# BMS_Current_Sense.net
KiCad netlist of a schematic drawn in Altium Designer
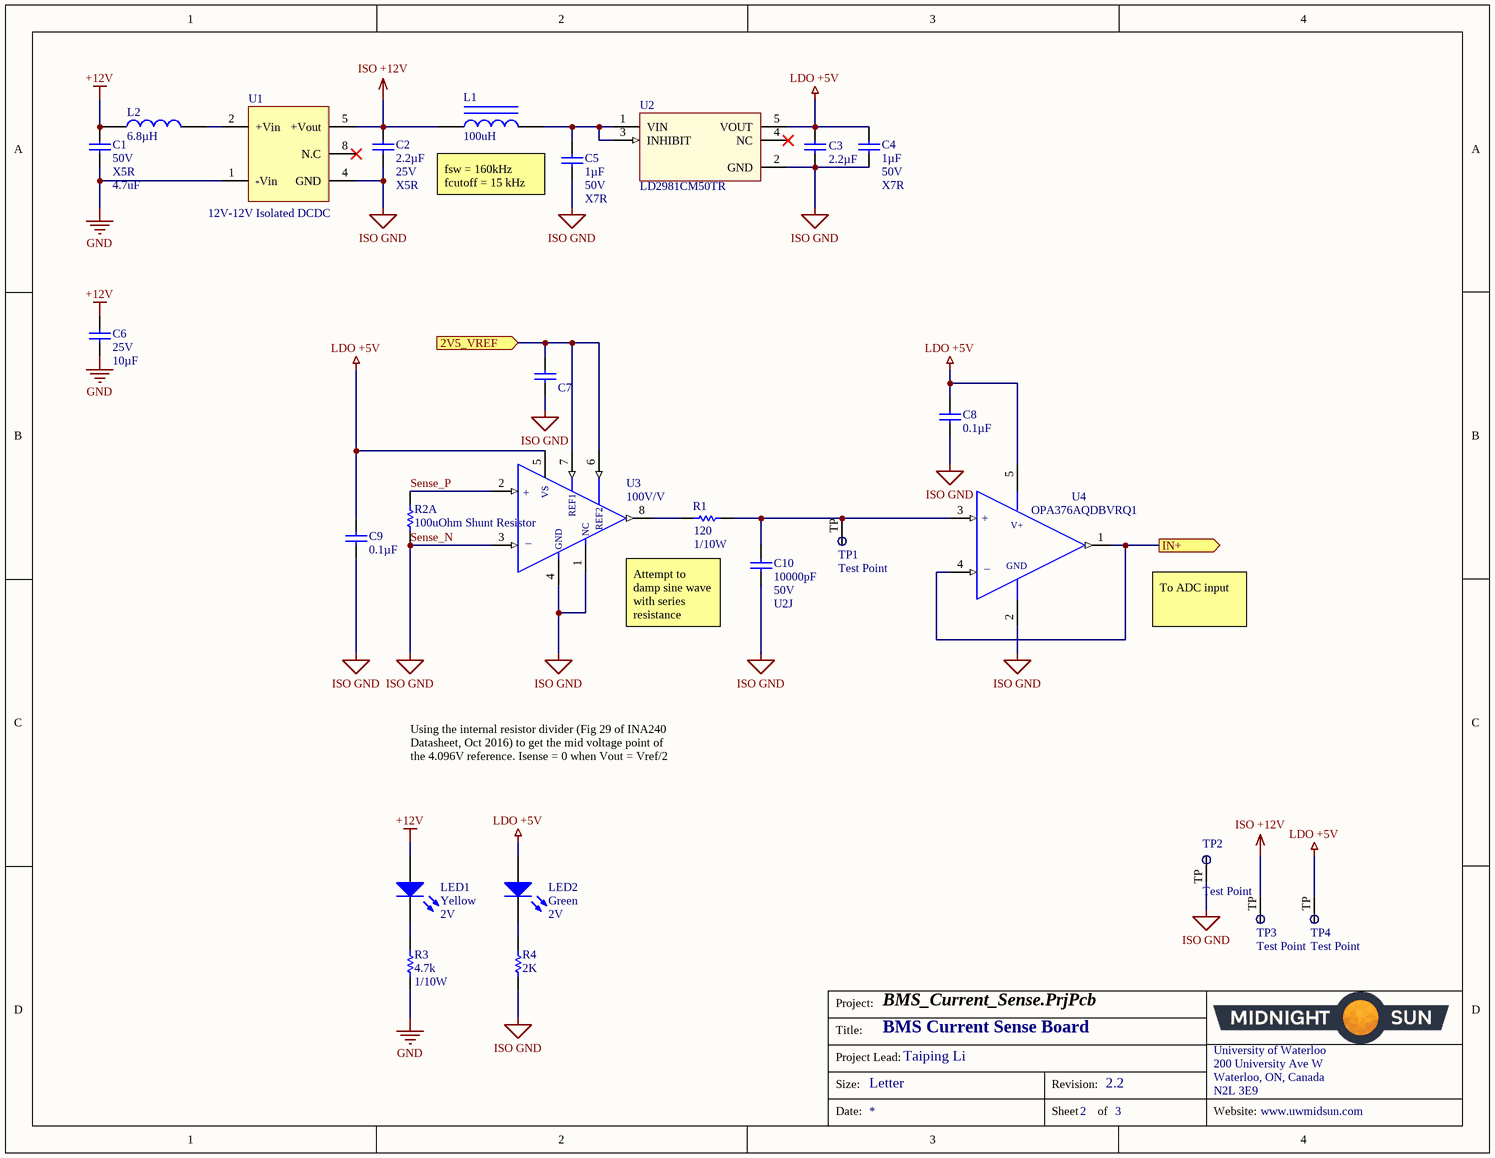
[diagram p0: BMS_Current_Sense.SchDoc]

(export (version "E")
  (design (tool "Eeschema 10.0.6"))
  (components
    (comp (ref "C1")
      (value "4.7uF")
      (footprint "CAP, 0805")
      (description "4.7µF ±20% 50V Ceramic Capacitor X5R 0805 (2012 Metric)")
      (fields
        (field (name "TOLERANCE") "±20%")
        (field (name "VOLTAGE - RATED") "50V")
        (field (name "TEMPERATURE COEFFICIENT") "X5R")
        (field (name "Comment") "CAP CER 4.7UF 50V 10% X5R 0805")
      )
      (libsource (lib "Schematic Diagrams") (part "CAP CER 4.7UF 50V 10% X5R 0805"))
    )
    (comp (ref "C2")
      (value "CAP CER 2.2UF 25V 10% X5R 0603")
      (footprint "CAP, 0603")
      (description "2.2µF ±10% 25V Ceramic Capacitor X5R 0603 (1608 Metric)")
      (fields
        (field (name "TOLERANCE") "±10%")
        (field (name "CAPACITANCE") "2.2µF")
        (field (name "VOLTAGE") "25V")
        (field (name "TEMPERATURE COEFFICIENT") "X5R")
      )
      (libsource (lib "Schematic Diagrams") (part "CAP CER 2.2UF 25V 10% X5R 0603"))
    )
    (comp (ref "C3")
      (value "CAP CER 2.2UF 25V 10% X5R 0603")
      (footprint "CAP, 0603")
      (description "2.2µF ±10% 25V Ceramic Capacitor X5R 0603 (1608 Metric)")
      (fields
        (field (name "TOLERANCE") "±10%")
        (field (name "CAPACITANCE") "2.2µF")
        (field (name "VOLTAGE") "25V")
      )
      (libsource (lib "Schematic Diagrams") (part "CAP CER 2.2UF 25V 10% X5R 0603"))
    )
    (comp (ref "C4")
      (value "CAP CER 1UF 50V 10% X7R 0603")
      (footprint "CAP, 0603")
      (description "1µF ±10% 50V Ceramic Capacitor X7R 0603 (1608 Metric)")
      (fields
        (field (name "TOLERANCE") "±10%")
        (field (name "CAPACITANCE") "1µF")
        (field (name "VOLTAGE") "50V")
        (field (name "TEMPERATURE COEFFICIENT") "X7R")
      )
      (libsource (lib "Schematic Diagrams") (part "CAP CER 1UF 50V 10% X7R 0603"))
    )
    (comp (ref "C5")
      (value "CAP CER 1UF 50V 10% X7R 0603")
      (footprint "CAP, 0603")
      (description "1µF ±10% 50V Ceramic Capacitor X7R 0603 (1608 Metric)")
      (fields
        (field (name "TOLERANCE") "±10%")
        (field (name "CAPACITANCE") "1µF")
        (field (name "VOLTAGE") "50V")
        (field (name "TEMPERATURE COEFFICIENT") "X7R")
      )
      (libsource (lib "Schematic Diagrams") (part "CAP CER 1UF 50V 10% X7R 0603"))
    )
    (comp (ref "C6")
      (value "CAP CER 10uF 25V 10% X5R 0805")
      (footprint "CAP, 0805")
      (description "10µF ±10% 25V Ceramic Capacitor X5R 0805 (2012 Metric)")
      (fields
        (field (name "MANUFACTURER") "Murata Electronics North America")
        (field (name "MANUFACTURER PART NUMBER") "GRM21BR61E106KA73L")
        (field (name "VOLTAGE - RATED") "25V")
        (field (name "CAPACITANCE") "10µF")
      )
      (libsource (lib "Schematic Diagrams") (part "CAP CER 10uF 25V 10% X5R 0805"))
    )
    (comp (ref "C7")
      (value "CAP CER 0.022UF 50V 10% X7R 0603")
      (footprint "CAP, 0603")
      (description "0.022µF ±10% 50V Ceramic Capacitor X7R 0603 (1608 Metric)")
      (fields (field (name "TOLERANCE") "±10%"))
      (libsource (lib "Schematic Diagrams") (part "CAP CER 0.022UF 50V 10% X7R 0603"))
    )
    (comp (ref "C8")
      (value "CAP CER 0.1UF 50V 10% X7R 0603")
      (footprint "CAP, 0603")
      (description "0.10µF ±10% 50V Ceramic Capacitor X7R 0603 (1608 Metric)")
      (fields
        (field (name "TOLERANCE") "±10%")
        (field (name "CAPACITANCE") "0.1µF")
        (field (name "VOLTAGE") "50V")
      )
      (libsource (lib "Schematic Diagrams") (part "CAP CER 0.1UF 50V 10% X7R 0603"))
    )
    (comp (ref "C9")
      (value "CAP CER 0.1UF 50V 10% X7R 0603")
      (footprint "CAP, 0603")
      (description "0.10µF ±10% 50V Ceramic Capacitor X7R 0603 (1608 Metric)")
      (fields
        (field (name "TOLERANCE") "±10%")
        (field (name "CAPACITANCE") "0.1µF")
        (field (name "VOLTAGE") "50V")
      )
      (libsource (lib "Schematic Diagrams") (part "CAP CER 0.1UF 50V 10% X7R 0603"))
    )
    (comp (ref "C10")
      (value "CAP CER 10nF 50V 5% X7R 0603")
      (footprint "CAP, 0603")
      (description "10000pF ±5% 50V Ceramic Capacitor U2J 0603 (1608 Metric)")
      (fields
        (field (name "TOLERANCE") "±5%")
        (field (name "CAPACITANCE") "10000pF")
        (field (name "VOLTAGE") "50V")
        (field (name "TEMPERATURE COEFFICIENT") "U2J")
      )
      (libsource (lib "Schematic Diagrams") (part "CAP CER 10nF 50V 5% X7R 0603"))
    )
    (comp (ref "L1")
      (value "100uH")
      (footprint "1210")
      (description "100µH Unshielded Wirewound Inductor 60mA 11 Ohm Max 1210 (3225 Metric)")
      (fields
        (field (name "MANUFACTURER") "EPCOS (TDK)")
        (field (name "MANUFACTURER PART NUMBER") "B82422T1104J000")
      )
      (libsource (lib "Schematic Diagrams") (part "IND 100uH 60mA 5% 1210"))
    )
    (comp (ref "L2")
      (value "IND 6.8uH 260mA 20% 1210")
      (footprint "NLFV32T-6R8M-EF/IND 6.8uH")
      (description "6.8µH Shielded Wirewound Inductor 260mA 204 mOhm Max 1210 (3225 Metric)")
      (fields (field (name "TOLERANCE") "±20%") (field (name "INDUCTANCE") "6.8µH"))
      (libsource (lib "Schematic Diagrams") (part "IND 6.8uH 260mA 20% 1210"))
    )
    (comp (ref "LED1")
      (value "LED YELLOW CLEAR 2.1V 0603")
      (footprint "LED_0603")
      (description "Yellow 590nm LED Indication - Discrete 2V 0603 (1608 Metric)")
      (fields
        (field (name "MANUFACTURER") "Wurth Electronics Inc.")
        (field (name "MANUFACTURER PART NUMBER") "150060YS75000")
        (field (name "COLOR") "Yellow")
        (field (name "VOLTAGE - FORWARD (VF) (TYP)") "2V")
      )
      (libsource (lib "Schematic Diagrams") (part "LED YELLOW CLEAR 2.1V 0603"))
    )
    (comp (ref "LED2")
      (value "LED GREEN CLEAR 2V 0603")
      (footprint "LED_0603")
      (description "Green 572nm LED Indication - Discrete 2V 0603 (1608 Metric)")
      (fields
        (field (name "MANUFACTURER") "Wurth Electronics Inc.")
        (field (name "MANUFACTURER PART NUMBER") "150060VS75000")
        (field (name "COLOR") "Green")
        (field (name "VOLTAGE - FORWARD (VF) (TYP)") "2V")
      )
      (libsource (lib "Schematic Diagrams") (part "LED GREEN CLEAR 2V 0603"))
    )
    (comp (ref "R1")
      (value "RES 120 OHM 1% 1/10W 0603")
      (footprint "RES, 0603")
      (description "RES SMD 120 OHM 1% 1/10W 0603")
      (fields
        (field (name "TOLERANCE") "±1%")
        (field (name "RESISTANCE") "120")
        (field (name "POWER") "1/10W")
      )
      (libsource (lib "Schematic Diagrams") (part "RES 120 OHM 1% 1/10W 0603"))
    )
    (comp (ref "R2")
      (value "100uOhm Shunt Resistor")
      (footprint "RES SHUNT 100UOHM 60MM")
      (fields (field (name "TOLERANCE") "±5%"))
      (libsource (lib "Schematic Diagrams") (part "RES SHUNT 100UOHM 5% 36W 60MM"))
    )
    (comp (ref "R3")
      (value "RES 4.7K OHM 1% 1/10W 0603")
      (footprint "RES, 0603")
      (description "4.7k Ohm ±1% 0.1W, 1/10W Chip Resistor 0603 (1608 Metric) Moisture Resistant Thick Film")
      (fields
        (field (name "TOLERANCE") "±1%")
        (field (name "RESISTANCE (OHMS)") "4.7k")
        (field (name "POWER (WATTS)") "1/10W")
      )
      (libsource (lib "Schematic Diagrams") (part "RES 4.7K OHM 1% 1/10W 0603"))
    )
    (comp (ref "R4")
      (value "2K")
      (footprint "RES, 0603")
      (description "2k Ohm ±1% 0.1W, 1/10W Chip Resistor 0603 (1608 Metric) Moisture Resistant Thick Film")
      (fields
        (field (name "MANUFACTURER") "Yageo")
        (field (name "MANUFACTURER PART NUMBER") "RC0603FR-072KL")
      )
      (libsource (lib "Schematic Diagrams") (part "RES 2K OHM 1% 1/10W 0603"))
    )
    (comp (ref "TP1")
      (value "Test Point")
      (footprint "Test Point")
      (libsource (lib "Schematic Diagrams") (part "Test Point"))
    )
    (comp (ref "TP2")
      (value "Test Point")
      (footprint "Test Point")
      (libsource (lib "Schematic Diagrams") (part "Test Point"))
    )
    (comp (ref "TP3")
      (value "Test Point")
      (footprint "Test Point")
      (libsource (lib "Schematic Diagrams") (part "Test Point"))
    )
    (comp (ref "TP4")
      (value "Test Point")
      (footprint "Test Point")
      (libsource (lib "Schematic Diagrams") (part "Test Point"))
    )
    (comp (ref "U1")
      (value "IC DCDC ISOLATED 12V 1W 8-SMD 5-LEAD")
      (footprint "IC, Isolated DCDC")
      (description "Isolated Module DC DC Converter 1 Output 12V 84mA 10.8V - 13.2V Input")
      (fields (field (name "POWER") "1W") (field (name "TYPE") "12V-12V Isolated DCDC"))
      (libsource (lib "Schematic Diagrams") (part "IC DCDC ISOLATED 12V 1W 8-SMD 5-LEAD"))
    )
    (comp (ref "U2")
      (value "IC REG LDO 5V 0.1A SOT23-5")
      (footprint "SOT95P280X145-5N")
      (description "Linear Voltage Regulator IC Positive Fixed Output 5V 100mA SOT-23-5")
      (fields (field (name "MANUFACTURER PART NUMBER 1") "LD2981CM50TR"))
      (libsource (lib "Schematic Diagrams") (part "IC REG LDO 5V 0.1A SOT23-5"))
    )
    (comp (ref "U3")
      (value "100V/V")
      (footprint "IC CURRENT AMPLIFIER INA240 TSSOP-8")
      (description "Current Sense Amplifier 1 Circuit 8-TSSOP")
      (libsource (lib "Schematic Diagrams") (part "IC CURRENT AMPLIFIER INA240 8-TSSOP"))
    )
    (comp (ref "U4")
      (value "IC OP AMP GEN PURPOSE RR 5.5MHZ SOT-23-5")
      (footprint "IC OP AMP GP RR 10MHZ SOT-23-5")
      (description "General Purpose Amplifier 1 Circuit Rail-to-Rail SOT-23-5")
      (fields
        (field (name "MANUFACTURER") "Texas Instruments")
        (field (name "MANUFACTURER PART NUMBER") "OPA376AQDBVRQ1")
      )
      (libsource (lib "Schematic Diagrams") (part "IC OP AMP GEN PURPOSE RR 5.5MHZ SOT-23-5"))
    )
  )
  (nets
    (net (code "1") (name "+12V") (class "Default")
      (node (ref "C1") (pin "1") (pinfunction "1_1") (pintype "passive"))
      (node (ref "C6") (pin "1") (pinfunction "1_1") (pintype "passive"))
      (node (ref "L2") (pin "1") (pinfunction "1_1") (pintype "passive"))
      (node (ref "LED1") (pin "1") (pinfunction "A_1") (pintype "passive"))
    )
    (net (code "2") (name "/2V5_VREF") (class "Default")
      (node (ref "C7") (pin "1") (pinfunction "1_1") (pintype "passive"))
      (node (ref "U3") (pin "6") (pinfunction "REF2_6") (pintype "input"))
      (node (ref "U3") (pin "7") (pinfunction "REF1_7") (pintype "input"))
    )
    (net (code "3") (name "/IN+") (class "Default")
      (node (ref "U4") (pin "1") (pinfunction "OUTPUT_1") (pintype "output"))
      (node (ref "U4") (pin "4") (pinfunction "-IN_4") (pintype "input"))
    )
    (net (code "4") (name "/Sense_P") (class "Default")
      (node (ref "R2") (pin "5") (pinfunction "5_5") (pintype "passive"))
      (node (ref "U3") (pin "2") (pinfunction "+IN_2") (pintype "input"))
    )
    (net (code "5") (name "GND") (class "Default")
      (node (ref "C1") (pin "2") (pinfunction "2_2") (pintype "passive"))
      (node (ref "C6") (pin "2") (pinfunction "2_2") (pintype "passive"))
      (node (ref "R3") (pin "2") (pinfunction "2_2") (pintype "passive"))
      (node (ref "U1") (pin "1") (pinfunction "-Vin_1") (pintype "passive"))
    )
    (net (code "6") (name "ISO +12V") (class "Default")
      (node (ref "C2") (pin "1") (pinfunction "1_1") (pintype "passive"))
      (node (ref "L1") (pin "1") (pinfunction "1_1") (pintype "passive"))
      (node (ref "TP3") (pin "TP") (pinfunction "1_TP") (pintype "passive"))
      (node (ref "U1") (pin "5") (pinfunction "+Vout_5") (pintype "passive"))
    )
    (net (code "7") (name "ISO GND") (class "Default")
      (node (ref "C10") (pin "2") (pinfunction "2_2") (pintype "passive"))
      (node (ref "C2") (pin "2") (pinfunction "2_2") (pintype "passive"))
      (node (ref "C3") (pin "2") (pinfunction "2_2") (pintype "passive"))
      (node (ref "C4") (pin "2") (pinfunction "2_2") (pintype "passive"))
      (node (ref "C5") (pin "2") (pinfunction "2_2") (pintype "passive"))
      (node (ref "C7") (pin "2") (pinfunction "2_2") (pintype "passive"))
      (node (ref "C8") (pin "2") (pinfunction "2_2") (pintype "passive"))
      (node (ref "C9") (pin "2") (pinfunction "2_2") (pintype "passive"))
      (node (ref "R2") (pin "6") (pinfunction "6_6") (pintype "passive"))
      (node (ref "R4") (pin "2") (pinfunction "2_2") (pintype "passive"))
      (node (ref "TP2") (pin "TP") (pinfunction "1_TP") (pintype "passive"))
      (node (ref "U1") (pin "4") (pinfunction "GND_4") (pintype "passive"))
      (node (ref "U2") (pin "2") (pinfunction "GND_2") (pintype "power_in"))
      (node (ref "U3") (pin "1") (pinfunction "NC_1") (pintype "power_in"))
      (node (ref "U3") (pin "3") (pinfunction "-IN_3") (pintype "input"))
      (node (ref "U3") (pin "4") (pinfunction "GND_4") (pintype "power_in"))
      (node (ref "U4") (pin "2") (pinfunction "VSS_2") (pintype "power_in"))
    )
    (net (code "8") (name "LDO +5V") (class "Default")
      (node (ref "C3") (pin "1") (pinfunction "1_1") (pintype "passive"))
      (node (ref "C4") (pin "1") (pinfunction "1_1") (pintype "passive"))
      (node (ref "C8") (pin "1") (pinfunction "1_1") (pintype "passive"))
      (node (ref "C9") (pin "1") (pinfunction "1_1") (pintype "passive"))
      (node (ref "LED2") (pin "1") (pinfunction "A_1") (pintype "passive"))
      (node (ref "TP4") (pin "TP") (pinfunction "1_TP") (pintype "passive"))
      (node (ref "U2") (pin "5") (pinfunction "VOUT_5") (pintype "power_in"))
      (node (ref "U3") (pin "5") (pinfunction "VS_5") (pintype "power_in"))
      (node (ref "U4") (pin "5") (pinfunction "VDD_5") (pintype "power_in"))
    )
    (net (code "9") (name "Net-(LED1-K)") (class "Default")
      (node (ref "LED1") (pin "2") (pinfunction "K_2") (pintype "passive"))
      (node (ref "R3") (pin "1") (pinfunction "1_1") (pintype "passive"))
    )
    (net (code "10") (name "Net-(LED2-K)") (class "Default")
      (node (ref "LED2") (pin "2") (pinfunction "K_2") (pintype "passive"))
      (node (ref "R4") (pin "1") (pinfunction "1_1") (pintype "passive"))
    )
    (net (code "11") (name "Net-(TP1-1)") (class "Default")
      (node (ref "C10") (pin "1") (pinfunction "1_1") (pintype "passive"))
      (node (ref "R1") (pin "2") (pinfunction "2_2") (pintype "passive"))
      (node (ref "TP1") (pin "TP") (pinfunction "1_TP") (pintype "passive"))
      (node (ref "U4") (pin "3") (pinfunction "+IN_3") (pintype "input"))
    )
    (net (code "12") (name "Net-(U1-+Vin)") (class "Default")
      (node (ref "L2") (pin "2") (pinfunction "2_2") (pintype "passive"))
      (node (ref "U1") (pin "2") (pinfunction "+Vin_2") (pintype "passive"))
    )
    (net (code "13") (name "Net-(U2-INHIBIT)") (class "Default")
      (node (ref "C5") (pin "1") (pinfunction "1_1") (pintype "passive"))
      (node (ref "L1") (pin "2") (pinfunction "2_2") (pintype "passive"))
      (node (ref "U2") (pin "1") (pinfunction "VIN_1") (pintype "power_in"))
      (node (ref "U2") (pin "3") (pinfunction "INHIBIT_3") (pintype "input"))
    )
    (net (code "14") (name "Net-(U3-OUTPUT)") (class "Default")
      (node (ref "R1") (pin "1") (pinfunction "1_1") (pintype "passive"))
      (node (ref "U3") (pin "8") (pinfunction "OUTPUT_8") (pintype "output"))
    )
    (net (code "15") (name "unconnected-(U1-N.C-Pad8)") (class "Default")
      (node (ref "U1") (pin "8") (pinfunction "N.C_8") (pintype "passive+no_connect"))
    )
    (net (code "16") (name "unconnected-(U2-NC-Pad4)") (class "Default")
      (node (ref "U2") (pin "4") (pinfunction "NC_4") (pintype "passive+no_connect"))
    )
  )
)
